# ADC.net
KiCad netlist of a schematic drawn in Altium Designer
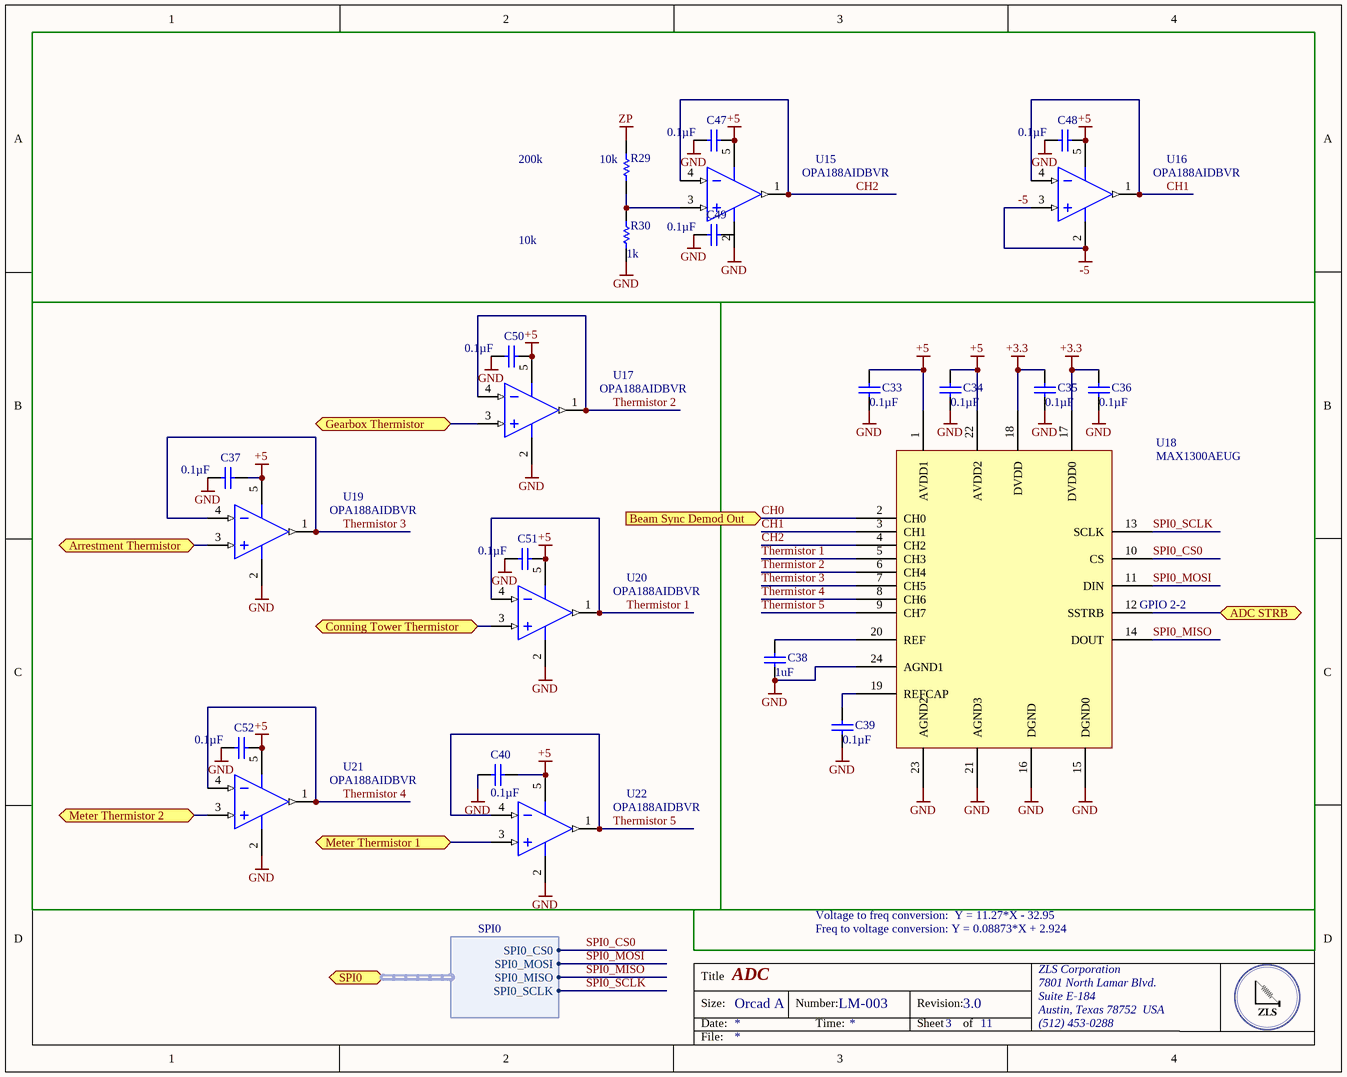
[diagram p0: ADC.SchDoc]

(export (version "E")
  (design (tool "Eeschema 10.0.6"))
  (components
    (comp (ref "C33")
      (value "CAP CER 0.1UF 25V X7R 0805")
      (footprint "CAPC0805(2012)145_N")
      (fields
        (field (name "MANUFACTURER") "Murata Electronics North America")
        (field (name "MANUFACTURER PART NUMBER") "GRM21BR71E104KA01L")
        (field (name "CAPACITANCE") "0.1µF")
        (field (name "TOLERANCE") "±10%")
      )
      (libsource (lib "Altium Content Vault") (part "CMP-1036-04795-1"))
    )
    (comp (ref "C34")
      (value "CAP CER 0.1UF 25V X7R 0805")
      (footprint "CAPC0805(2012)145_N")
      (fields
        (field (name "MANUFACTURER") "Murata Electronics North America")
        (field (name "MANUFACTURER PART NUMBER") "GRM21BR71E104KA01L")
        (field (name "CAPACITANCE") "0.1µF")
        (field (name "TOLERANCE") "±10%")
      )
      (libsource (lib "Altium Content Vault") (part "CMP-1036-04795-1"))
    )
    (comp (ref "C35")
      (value "CAP CER 0.1UF 25V X7R 0805")
      (footprint "CAPC0805(2012)145_N")
      (fields
        (field (name "MANUFACTURER") "Murata Electronics North America")
        (field (name "MANUFACTURER PART NUMBER") "GRM21BR71E104KA01L")
        (field (name "CAPACITANCE") "0.1µF")
        (field (name "TOLERANCE") "±10%")
      )
      (libsource (lib "Altium Content Vault") (part "CMP-1036-04795-1"))
    )
    (comp (ref "C36")
      (value "CAP CER 0.1UF 25V X7R 0805")
      (footprint "CAPC0805(2012)145_N")
      (fields
        (field (name "MANUFACTURER") "Murata Electronics North America")
        (field (name "MANUFACTURER PART NUMBER") "GRM21BR71E104KA01L")
        (field (name "CAPACITANCE") "0.1µF")
        (field (name "TOLERANCE") "±10%")
      )
      (libsource (lib "Altium Content Vault") (part "CMP-1036-04795-1"))
    )
    (comp (ref "C37")
      (value "CAP CER 0.1UF 16V X7R 0805")
      (footprint "CAPC0805(2012)145_N")
      (fields
        (field (name "TOLERANCE") "±10%")
        (field (name "MANUFACTURER") "Murata Electronics North America")
        (field (name "MANUFACTURER PART NUMBER") "GRM219R71C104KA01D")
        (field (name "CAPACITANCE") "0.1µF")
      )
      (libsource (lib "Altium Content Vault") (part "CMP-1036-04795-1"))
    )
    (comp (ref "C38")
      (value "CAP CER 1UF 16V X7R 0805")
      (footprint "CAPC0805(2012)145_N")
      (fields
        (field (name "MANUFACTURER") "Kemet")
        (field (name "MANUFACTURER PART NUMBER") "C0805X105K4RACTU")
        (field (name "CAPACITANCE") "1uF")
        (field (name "TOLERANCE") "10%")
      )
      (libsource (lib "Altium Content Vault") (part "CMP-1036-04795-1"))
    )
    (comp (ref "C39")
      (value "CAP CER 0.1UF 16V X7R 0805")
      (footprint "CAPC0805(2012)145_N")
      (fields
        (field (name "TOLERANCE") "±10%")
        (field (name "MANUFACTURER") "Murata Electronics North America")
        (field (name "MANUFACTURER PART NUMBER") "GRM219R71C104KA01D")
        (field (name "CAPACITANCE") "0.1µF")
      )
      (libsource (lib "Altium Content Vault") (part "CMP-1036-04795-1"))
    )
    (comp (ref "C40")
      (value "CAP CER 0.1UF 16V X7R 0805")
      (footprint "CAPC0805(2012)145_N")
      (fields
        (field (name "TOLERANCE") "±10%")
        (field (name "MANUFACTURER") "Murata Electronics North America")
        (field (name "MANUFACTURER PART NUMBER") "GRM219R71C104KA01D")
        (field (name "CAPACITANCE") "0.1µF")
      )
      (libsource (lib "Altium Content Vault") (part "CMP-1036-04795-1"))
    )
    (comp (ref "C47")
      (value "CAP CER 0.1UF 16V X7R 0805")
      (footprint "CAPC0805(2012)145_N")
      (fields
        (field (name "TOLERANCE") "±10%")
        (field (name "MANUFACTURER") "Murata Electronics North America")
        (field (name "MANUFACTURER PART NUMBER") "GRM219R71C104KA01D")
        (field (name "CAPACITANCE") "0.1µF")
      )
      (libsource (lib "Altium Content Vault") (part "CMP-1036-04795-1"))
    )
    (comp (ref "C48")
      (value "CAP CER 0.1UF 16V X7R 0805")
      (footprint "CAPC0805(2012)145_N")
      (fields
        (field (name "TOLERANCE") "±10%")
        (field (name "MANUFACTURER") "Murata Electronics North America")
        (field (name "MANUFACTURER PART NUMBER") "GRM219R71C104KA01D")
        (field (name "CAPACITANCE") "0.1µF")
      )
      (libsource (lib "Altium Content Vault") (part "CMP-1036-04795-1"))
    )
    (comp (ref "C49")
      (value "CAP CER 0.1UF 16V X7R 0805")
      (footprint "CAPC0805(2012)145_N")
      (fields
        (field (name "TOLERANCE") "±10%")
        (field (name "MANUFACTURER") "Murata Electronics North America")
        (field (name "MANUFACTURER PART NUMBER") "GRM219R71C104KA01D")
        (field (name "CAPACITANCE") "0.1µF")
      )
      (libsource (lib "Altium Content Vault") (part "CMP-1036-04795-1"))
    )
    (comp (ref "C50")
      (value "CAP CER 0.1UF 16V X7R 0805")
      (footprint "CAPC0805(2012)145_N")
      (fields
        (field (name "TOLERANCE") "±10%")
        (field (name "MANUFACTURER") "Murata Electronics North America")
        (field (name "MANUFACTURER PART NUMBER") "GRM219R71C104KA01D")
        (field (name "CAPACITANCE") "0.1µF")
      )
      (libsource (lib "Altium Content Vault") (part "CMP-1036-04795-1"))
    )
    (comp (ref "C51")
      (value "CAP CER 0.1UF 16V X7R 0805")
      (footprint "CAPC0805(2012)145_N")
      (fields
        (field (name "TOLERANCE") "±10%")
        (field (name "MANUFACTURER") "Murata Electronics North America")
        (field (name "MANUFACTURER PART NUMBER") "GRM219R71C104KA01D")
        (field (name "CAPACITANCE") "0.1µF")
      )
      (libsource (lib "Altium Content Vault") (part "CMP-1036-04795-1"))
    )
    (comp (ref "C52")
      (value "CAP CER 0.1UF 16V X7R 0805")
      (footprint "CAPC0805(2012)145_N")
      (fields
        (field (name "TOLERANCE") "±10%")
        (field (name "MANUFACTURER") "Murata Electronics North America")
        (field (name "MANUFACTURER PART NUMBER") "GRM219R71C104KA01D")
        (field (name "CAPACITANCE") "0.1µF")
      )
      (libsource (lib "Altium Content Vault") (part "CMP-1036-04795-1"))
    )
    (comp (ref "R29")
      (value "RES SMD 10K OHM 1% 1/8W 0805")
      (footprint "RESC0805(2012)_M")
      (fields
        (field (name "MANUFACTURER") "Vishay Dale")
        (field (name "MANUFACTURER PART NUMBER") "CRCW080510K0FKTA")
        (field (name "RESISTANCE (OHMS)") "10k")
        (field (name "TOLERANCE") "±1%")
      )
      (libsource (lib "Altium Content Vault") (part "CMP-1013-00017-1"))
    )
    (comp (ref "R30")
      (value "RES SMD 1K OHM 1% 1/8W 0805")
      (footprint "RESC0805(2012)_M")
      (fields
        (field (name "MANUFACTURER") "Vishay Dale")
        (field (name "MANUFACTURER PART NUMBER") "CRCW08051K00FKTA")
        (field (name "RESISTANCE (OHMS)") "1k")
        (field (name "TOLERANCE") "±1%")
      )
      (libsource (lib "Altium Content Vault") (part "CMP-1013-00017-1"))
    )
    (comp (ref "U15")
      (value "OPA188AIDBVR")
      (footprint "DBV0005A_M")
      (fields (field (name "MANUFACTURER") "Texas Instruments"))
      (libsource (lib "Altium Content Vault") (part "CMP-0809-00005-2"))
    )
    (comp (ref "U16")
      (value "OPA188AIDBVR")
      (footprint "DBV0005A_M")
      (fields (field (name "MANUFACTURER") "Texas Instruments"))
      (libsource (lib "Altium Content Vault") (part "CMP-0809-00005-2"))
    )
    (comp (ref "U17")
      (value "OPA188AIDBVR")
      (footprint "DBV0005A_M")
      (fields (field (name "MANUFACTURER") "Texas Instruments"))
      (libsource (lib "Altium Content Vault") (part "CMP-0809-00005-2"))
    )
    (comp (ref "U18")
      (value "MAX1300AEUG")
      (footprint "TSOP65P640X90-24N")
      (description "IC ADC 16BIT SRL 115KSPS 24TSSOP")
      (libsource (lib "ZLS_LIB") (part "MAX1300AEUG"))
    )
    (comp (ref "U19")
      (value "OPA188AIDBVR")
      (footprint "DBV0005A_M")
      (fields (field (name "MANUFACTURER") "Texas Instruments"))
      (libsource (lib "Altium Content Vault") (part "CMP-0809-00005-2"))
    )
    (comp (ref "U20")
      (value "OPA188AIDBVR")
      (footprint "DBV0005A_M")
      (fields (field (name "MANUFACTURER") "Texas Instruments"))
      (libsource (lib "Altium Content Vault") (part "CMP-0809-00005-2"))
    )
    (comp (ref "U21")
      (value "OPA188AIDBVR")
      (footprint "DBV0005A_M")
      (fields (field (name "MANUFACTURER") "Texas Instruments"))
      (libsource (lib "Altium Content Vault") (part "CMP-0809-00005-2"))
    )
    (comp (ref "U22")
      (value "OPA188AIDBVR")
      (footprint "DBV0005A_M")
      (fields (field (name "MANUFACTURER") "Texas Instruments"))
      (libsource (lib "Altium Content Vault") (part "CMP-0809-00005-2"))
    )
  )
  (nets
    (net (code "2") (name "+3.3") (class "Default")
      (node (ref "C35") (pin "1") (pinfunction "1_1") (pintype "passive"))
      (node (ref "C36") (pin "1") (pinfunction "1_1") (pintype "passive"))
      (node (ref "U18") (pin "17") (pinfunction "DVDD0_17") (pintype "passive"))
      (node (ref "U18") (pin "18") (pinfunction "DVDD_18") (pintype "passive"))
    )
    (net (code "3") (name "+5") (class "Default")
      (node (ref "C33") (pin "1") (pinfunction "1_1") (pintype "passive"))
      (node (ref "C34") (pin "1") (pinfunction "1_1") (pintype "passive"))
      (node (ref "C37") (pin "2") (pinfunction "2_2") (pintype "passive"))
      (node (ref "C40") (pin "2") (pinfunction "2_2") (pintype "passive"))
      (node (ref "C47") (pin "2") (pinfunction "2_2") (pintype "passive"))
      (node (ref "C48") (pin "2") (pinfunction "2_2") (pintype "passive"))
      (node (ref "C50") (pin "2") (pinfunction "2_2") (pintype "passive"))
      (node (ref "C51") (pin "2") (pinfunction "2_2") (pintype "passive"))
      (node (ref "C52") (pin "2") (pinfunction "2_2") (pintype "passive"))
      (node (ref "U15") (pin "5") (pinfunction "V+_5") (pintype "power_in"))
      (node (ref "U16") (pin "5") (pinfunction "V+_5") (pintype "power_in"))
      (node (ref "U17") (pin "5") (pinfunction "V+_5") (pintype "power_in"))
      (node (ref "U18") (pin "1") (pinfunction "AVDD1_1") (pintype "passive"))
      (node (ref "U18") (pin "22") (pinfunction "AVDD2_22") (pintype "passive"))
      (node (ref "U19") (pin "5") (pinfunction "V+_5") (pintype "power_in"))
      (node (ref "U20") (pin "5") (pinfunction "V+_5") (pintype "power_in"))
      (node (ref "U21") (pin "5") (pinfunction "V+_5") (pintype "power_in"))
      (node (ref "U22") (pin "5") (pinfunction "V+_5") (pintype "power_in"))
    )
    (net (code "4") (name "-5") (class "Default")
      (node (ref "U16") (pin "2") (pinfunction "V-_2") (pintype "power_in"))
      (node (ref "U16") (pin "3") (pinfunction "IN+_3") (pintype "input"))
    )
    (net (code "5") (name "/ADC STRB") (class "Default")
      (node (ref "U18") (pin "12") (pinfunction "SSTRB_12") (pintype "passive"))
    )
    (net (code "6") (name "/Arrestment Thermistor") (class "Default")
      (node (ref "U19") (pin "3") (pinfunction "IN+_3") (pintype "input"))
    )
    (net (code "7") (name "/CH0") (class "Default")
      (node (ref "U18") (pin "2") (pinfunction "CH0_2") (pintype "passive"))
    )
    (net (code "8") (name "/CH1") (class "Default")
      (node (ref "U16") (pin "1") (pinfunction "OUT_1") (pintype "output"))
      (node (ref "U16") (pin "4") (pinfunction "IN-_4") (pintype "input"))
      (node (ref "U18") (pin "3") (pinfunction "CH1_3") (pintype "passive"))
    )
    (net (code "9") (name "/CH2") (class "Default")
      (node (ref "U15") (pin "1") (pinfunction "OUT_1") (pintype "output"))
      (node (ref "U15") (pin "4") (pinfunction "IN-_4") (pintype "input"))
      (node (ref "U18") (pin "4") (pinfunction "CH2_4") (pintype "passive"))
    )
    (net (code "10") (name "/Conning Tower Thermistor") (class "Default")
      (node (ref "U20") (pin "3") (pinfunction "IN+_3") (pintype "input"))
    )
    (net (code "11") (name "/Gearbox Thermistor") (class "Default")
      (node (ref "U17") (pin "3") (pinfunction "IN+_3") (pintype "input"))
    )
    (net (code "12") (name "/Meter Thermistor 1") (class "Default")
      (node (ref "U22") (pin "3") (pinfunction "IN+_3") (pintype "input"))
    )
    (net (code "13") (name "/Meter Thermistor 2") (class "Default")
      (node (ref "U21") (pin "3") (pinfunction "IN+_3") (pintype "input"))
    )
    (net (code "14") (name "/SPI0_CS0") (class "Default")
      (node (ref "U18") (pin "10") (pinfunction "CS_10") (pintype "passive"))
    )
    (net (code "15") (name "/SPI0_MISO") (class "Default")
      (node (ref "U18") (pin "14") (pinfunction "DOUT_14") (pintype "passive"))
    )
    (net (code "16") (name "/SPI0_MOSI") (class "Default")
      (node (ref "U18") (pin "11") (pinfunction "DIN_11") (pintype "passive"))
    )
    (net (code "17") (name "/SPI0_SCLK") (class "Default")
      (node (ref "U18") (pin "13") (pinfunction "SCLK_13") (pintype "passive"))
    )
    (net (code "18") (name "/Thermistor 1") (class "Default")
      (node (ref "U18") (pin "5") (pinfunction "CH3_5") (pintype "passive"))
      (node (ref "U20") (pin "1") (pinfunction "OUT_1") (pintype "output"))
      (node (ref "U20") (pin "4") (pinfunction "IN-_4") (pintype "input"))
    )
    (net (code "19") (name "/Thermistor 2") (class "Default")
      (node (ref "U17") (pin "1") (pinfunction "OUT_1") (pintype "output"))
      (node (ref "U17") (pin "4") (pinfunction "IN-_4") (pintype "input"))
      (node (ref "U18") (pin "6") (pinfunction "CH4_6") (pintype "passive"))
    )
    (net (code "20") (name "/Thermistor 3") (class "Default")
      (node (ref "U18") (pin "7") (pinfunction "CH5_7") (pintype "passive"))
      (node (ref "U19") (pin "1") (pinfunction "OUT_1") (pintype "output"))
      (node (ref "U19") (pin "4") (pinfunction "IN-_4") (pintype "input"))
    )
    (net (code "21") (name "/Thermistor 4") (class "Default")
      (node (ref "U18") (pin "8") (pinfunction "CH6_8") (pintype "passive"))
      (node (ref "U21") (pin "1") (pinfunction "OUT_1") (pintype "output"))
      (node (ref "U21") (pin "4") (pinfunction "IN-_4") (pintype "input"))
    )
    (net (code "22") (name "/Thermistor 5") (class "Default")
      (node (ref "U18") (pin "9") (pinfunction "CH7_9") (pintype "passive"))
      (node (ref "U22") (pin "1") (pinfunction "OUT_1") (pintype "output"))
      (node (ref "U22") (pin "4") (pinfunction "IN-_4") (pintype "input"))
    )
    (net (code "24") (name "GND") (class "Default")
      (node (ref "C33") (pin "2") (pinfunction "2_2") (pintype "passive"))
      (node (ref "C34") (pin "2") (pinfunction "2_2") (pintype "passive"))
      (node (ref "C35") (pin "2") (pinfunction "2_2") (pintype "passive"))
      (node (ref "C36") (pin "2") (pinfunction "2_2") (pintype "passive"))
      (node (ref "C37") (pin "1") (pinfunction "1_1") (pintype "passive"))
      (node (ref "C38") (pin "2") (pinfunction "2_2") (pintype "passive"))
      (node (ref "C39") (pin "2") (pinfunction "2_2") (pintype "passive"))
      (node (ref "C40") (pin "1") (pinfunction "1_1") (pintype "passive"))
      (node (ref "C47") (pin "1") (pinfunction "1_1") (pintype "passive"))
      (node (ref "C48") (pin "1") (pinfunction "1_1") (pintype "passive"))
      (node (ref "C49") (pin "1") (pinfunction "1_1") (pintype "passive"))
      (node (ref "C50") (pin "1") (pinfunction "1_1") (pintype "passive"))
      (node (ref "C51") (pin "1") (pinfunction "1_1") (pintype "passive"))
      (node (ref "C52") (pin "1") (pinfunction "1_1") (pintype "passive"))
      (node (ref "R30") (pin "1") (pinfunction "1_1") (pintype "passive"))
      (node (ref "U15") (pin "2") (pinfunction "V-_2") (pintype "power_in"))
      (node (ref "U17") (pin "2") (pinfunction "V-_2") (pintype "power_in"))
      (node (ref "U18") (pin "15") (pinfunction "DGND0_15") (pintype "passive"))
      (node (ref "U18") (pin "16") (pinfunction "DGND_16") (pintype "passive"))
      (node (ref "U18") (pin "21") (pinfunction "AGND3_21") (pintype "passive"))
      (node (ref "U18") (pin "23") (pinfunction "AGND2_23") (pintype "passive"))
      (node (ref "U18") (pin "24") (pinfunction "AGND1_24") (pintype "passive"))
      (node (ref "U19") (pin "2") (pinfunction "V-_2") (pintype "power_in"))
      (node (ref "U20") (pin "2") (pinfunction "V-_2") (pintype "power_in"))
      (node (ref "U21") (pin "2") (pinfunction "V-_2") (pintype "power_in"))
      (node (ref "U22") (pin "2") (pinfunction "V-_2") (pintype "power_in"))
    )
    (net (code "25") (name "Net-(U15-IN+)") (class "Default")
      (node (ref "R29") (pin "1") (pinfunction "1_1") (pintype "passive"))
      (node (ref "R30") (pin "2") (pinfunction "2_2") (pintype "passive"))
      (node (ref "U15") (pin "3") (pinfunction "IN+_3") (pintype "input"))
    )
    (net (code "26") (name "Net-(U18-REF)") (class "Default")
      (node (ref "C38") (pin "1") (pinfunction "1_1") (pintype "passive"))
      (node (ref "U18") (pin "20") (pinfunction "REF_20") (pintype "passive"))
    )
    (net (code "27") (name "Net-(U18-REFCAP)") (class "Default")
      (node (ref "C39") (pin "1") (pinfunction "1_1") (pintype "passive"))
      (node (ref "U18") (pin "19") (pinfunction "REFCAP_19") (pintype "passive"))
    )
    (net (code "28") (name "ZP") (class "Default")
      (node (ref "R29") (pin "2") (pinfunction "2_2") (pintype "passive"))
    )
    (net (code "29") (name "unconnected-(C49-Pad2)") (class "Default")
      (node (ref "C49") (pin "2") (pinfunction "2_2") (pintype "passive"))
    )
  )
)
